# Controle_placa_potencia.net
KiCad netlist of a schematic drawn in Altium Designer
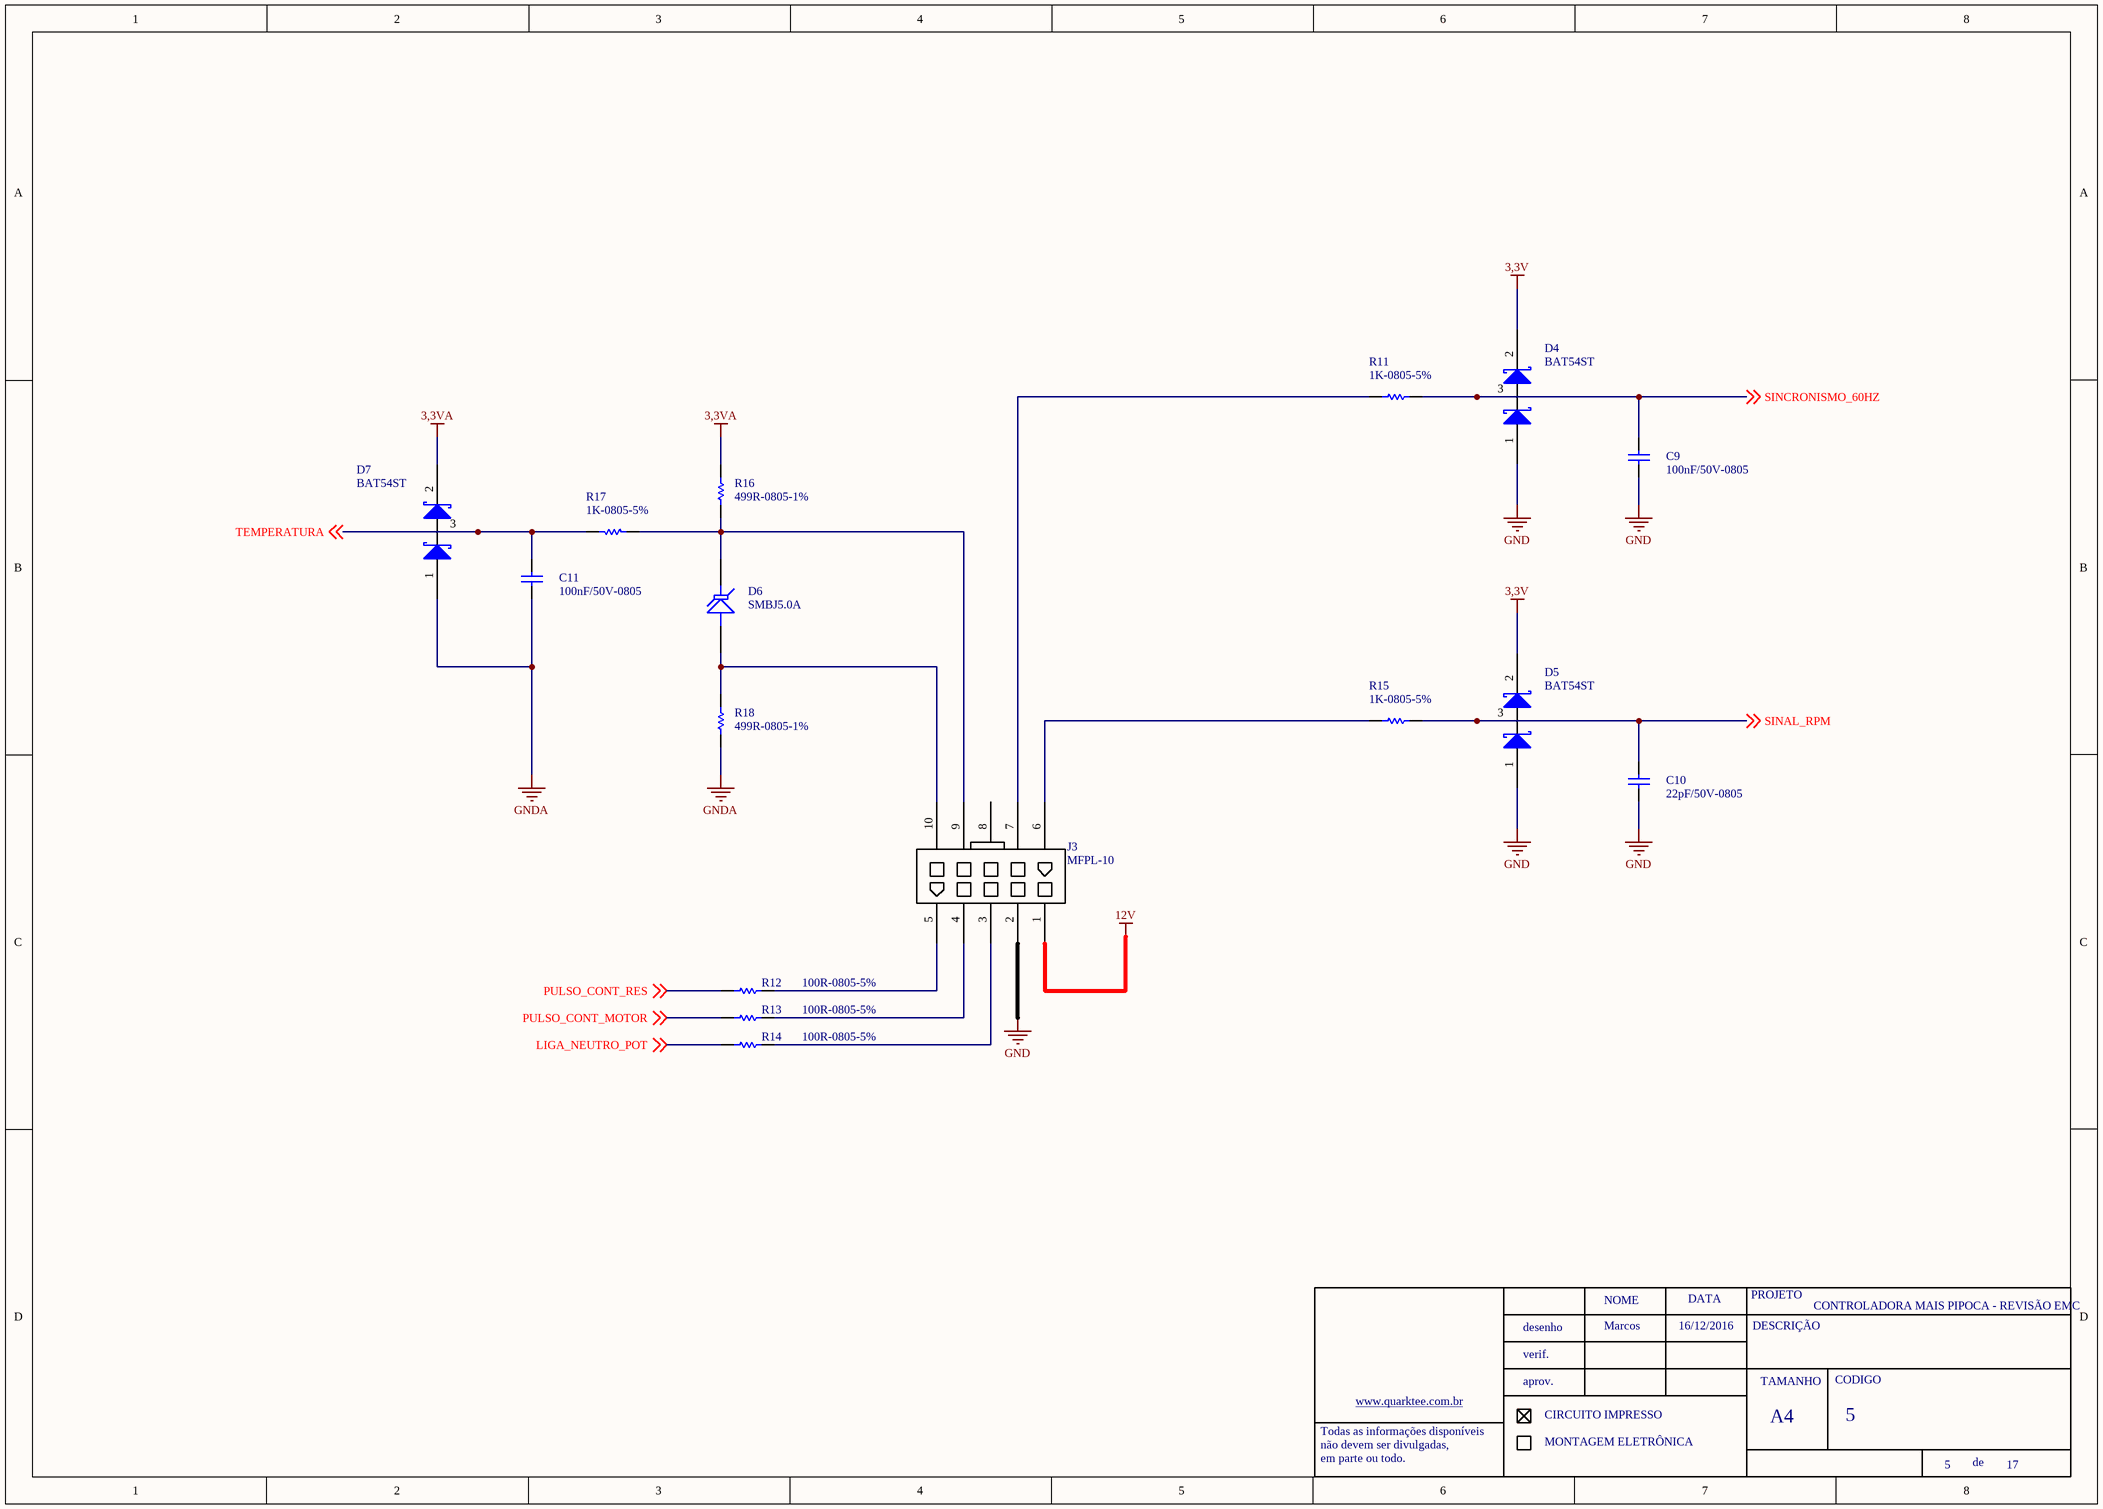
[diagram p0: Controle_placa_potencia.SchDoc]

(export (version "E")
  (design (tool "Eeschema 10.0.6"))
  (components
    (comp (ref "C9")
      (value "100nF/50V-0805")
      (footprint "0805-REVISADO ONDA")
      (libsource (lib "AquinoLib") (part "100nF/50-0805-NPO"))
    )
    (comp (ref "C10")
      (value "22pF/50V-0805")
      (footprint "0805-REVISADO ONDA")
      (description "100nF/50V-0805")
      (libsource (lib "AquinoLib") (part "100nF/50-0805-NPO"))
    )
    (comp (ref "C11")
      (value "100nF/50V-0805")
      (footprint "0805-REVISADO ONDA")
      (libsource (lib "AquinoLib") (part "100nF/50-0805-NPO"))
    )
    (comp (ref "D4")
      (value "BAT54ST")
      (footprint "SOT23 - REVISADO ONDA")
      (libsource (lib "AquinoLib") (part "BAT54ST"))
    )
    (comp (ref "D5")
      (value "BAT54ST")
      (footprint "SOT23 - REVISADO ONDA")
      (libsource (lib "AquinoLib") (part "BAT54ST"))
    )
    (comp (ref "D6")
      (value "SMBJ5.0A")
      (footprint "SMA DIODES")
      (libsource (lib "AquinoLib") (part "SMBJ5.0A"))
    )
    (comp (ref "D7")
      (value "BAT54ST")
      (footprint "SOT23 - REVISADO ONDA")
      (libsource (lib "AquinoLib") (part "BAT54ST"))
    )
    (comp (ref "J3") (value "MFPL-10") (libsource (lib "AquinoLib") (part "MFPL-10")))
    (comp (ref "R11")
      (value "1K-0805-5%")
      (footprint "0805-REVISADO ONDA")
      (libsource (lib "AquinoLib") (part "1K-0805-5%"))
    )
    (comp (ref "R12")
      (value "100R-0805-5%")
      (footprint "0805-REVISADO ONDA")
      (libsource (lib "AquinoLib") (part "100R-0805-5%"))
    )
    (comp (ref "R13")
      (value "100R-0805-5%")
      (footprint "0805-REVISADO ONDA")
      (libsource (lib "AquinoLib") (part "100R-0805-5%"))
    )
    (comp (ref "R14")
      (value "100R-0805-5%")
      (footprint "0805-REVISADO ONDA")
      (libsource (lib "AquinoLib") (part "100R-0805-5%"))
    )
    (comp (ref "R15")
      (value "1K-0805-5%")
      (footprint "0805-REVISADO ONDA")
      (libsource (lib "AquinoLib") (part "1K-0805-5%"))
    )
    (comp (ref "R16")
      (value "499R-0805-1%")
      (footprint "0805-REVISADO ONDA")
      (description "10K-0805-5%")
      (libsource (lib "AquinoLib") (part "10K-0805-5%"))
    )
    (comp (ref "R17")
      (value "1K-0805-5%")
      (footprint "0805-REVISADO ONDA")
      (libsource (lib "AquinoLib") (part "1K-0805-5%"))
    )
    (comp (ref "R18")
      (value "499R-0805-1%")
      (footprint "0805-REVISADO ONDA")
      (description "10K-0805-5%")
      (libsource (lib "AquinoLib") (part "10K-0805-5%"))
    )
  )
  (nets
    (net (code "1") (name "3,3V") (class "Default")
      (node (ref "D4") (pin "2") (pinfunction "2_2") (pintype "passive"))
      (node (ref "D5") (pin "2") (pinfunction "2_2") (pintype "passive"))
    )
    (net (code "2") (name "3,3VA") (class "Default")
      (node (ref "D7") (pin "2") (pinfunction "2_2") (pintype "passive"))
      (node (ref "R16") (pin "2") (pinfunction "2_2") (pintype "passive"))
    )
    (net (code "3") (name "12V") (class "Default")
      (node (ref "J3") (pin "1") (pinfunction "1_1") (pintype "passive"))
    )
    (net (code "4") (name "GND") (class "Default")
      (node (ref "C10") (pin "2") (pinfunction "2_2") (pintype "passive"))
      (node (ref "C9") (pin "2") (pinfunction "2_2") (pintype "passive"))
      (node (ref "D4") (pin "1") (pinfunction "1_1") (pintype "passive"))
      (node (ref "D5") (pin "1") (pinfunction "1_1") (pintype "passive"))
      (node (ref "J3") (pin "2") (pinfunction "2_2") (pintype "passive"))
    )
    (net (code "5") (name "GNDA") (class "Default")
      (node (ref "C11") (pin "1") (pinfunction "1_1") (pintype "passive"))
      (node (ref "D7") (pin "1") (pinfunction "1_1") (pintype "passive"))
      (node (ref "R18") (pin "1") (pinfunction "1_1") (pintype "passive"))
    )
    (net (code "6") (name "LIGA_NEUTRO_POT") (class "Default")
      (node (ref "R14") (pin "1") (pinfunction "1_1") (pintype "passive"))
    )
    (net (code "7") (name "Net-(D6-A)") (class "Default")
      (node (ref "D6") (pin "1") (pinfunction "A_1") (pintype "passive"))
      (node (ref "J3") (pin "10") (pinfunction "10_10") (pintype "passive"))
      (node (ref "R18") (pin "2") (pinfunction "2_2") (pintype "passive"))
    )
    (net (code "8") (name "Net-(D6-K)") (class "Default")
      (node (ref "D6") (pin "2") (pinfunction "K_2") (pintype "passive"))
      (node (ref "J3") (pin "9") (pinfunction "9_9") (pintype "passive"))
      (node (ref "R16") (pin "1") (pinfunction "1_1") (pintype "passive"))
      (node (ref "R17") (pin "1") (pinfunction "1_1") (pintype "passive"))
    )
    (net (code "9") (name "Net-(J3-Pad3)") (class "Default")
      (node (ref "J3") (pin "3") (pinfunction "3_3") (pintype "passive"))
      (node (ref "R14") (pin "2") (pinfunction "2_2") (pintype "passive"))
    )
    (net (code "10") (name "Net-(J3-Pad4)") (class "Default")
      (node (ref "J3") (pin "4") (pinfunction "4_4") (pintype "passive"))
      (node (ref "R13") (pin "2") (pinfunction "2_2") (pintype "passive"))
    )
    (net (code "11") (name "Net-(J3-Pad5)") (class "Default")
      (node (ref "J3") (pin "5") (pinfunction "5_5") (pintype "passive"))
      (node (ref "R12") (pin "1") (pinfunction "1_1") (pintype "passive"))
    )
    (net (code "12") (name "Net-(J3-Pad6)") (class "Default")
      (node (ref "J3") (pin "6") (pinfunction "6_6") (pintype "passive"))
      (node (ref "R15") (pin "1") (pinfunction "1_1") (pintype "passive"))
    )
    (net (code "13") (name "Net-(J3-Pad7)") (class "Default")
      (node (ref "J3") (pin "7") (pinfunction "7_7") (pintype "passive"))
      (node (ref "R11") (pin "1") (pinfunction "1_1") (pintype "passive"))
    )
    (net (code "14") (name "PULSO_CONT_MOTOR") (class "Default")
      (node (ref "R13") (pin "1") (pinfunction "1_1") (pintype "passive"))
    )
    (net (code "15") (name "PULSO_CONT_RES") (class "Default")
      (node (ref "R12") (pin "2") (pinfunction "2_2") (pintype "passive"))
    )
    (net (code "16") (name "SINAL_RPM") (class "Default")
      (node (ref "C10") (pin "1") (pinfunction "1_1") (pintype "passive"))
      (node (ref "D5") (pin "3") (pinfunction "3_3") (pintype "passive"))
      (node (ref "R15") (pin "2") (pinfunction "2_2") (pintype "passive"))
    )
    (net (code "17") (name "SINCRONISMO_60HZ") (class "Default")
      (node (ref "C9") (pin "1") (pinfunction "1_1") (pintype "passive"))
      (node (ref "D4") (pin "3") (pinfunction "3_3") (pintype "passive"))
      (node (ref "R11") (pin "2") (pinfunction "2_2") (pintype "passive"))
    )
    (net (code "18") (name "TEMPERATURA") (class "Default")
      (node (ref "C11") (pin "2") (pinfunction "2_2") (pintype "passive"))
      (node (ref "D7") (pin "3") (pinfunction "3_3") (pintype "passive"))
      (node (ref "R17") (pin "2") (pinfunction "2_2") (pintype "passive"))
    )
    (net (code "19") (name "unconnected-(J3-Pad8)") (class "Default")
      (node (ref "J3") (pin "8") (pinfunction "8_8") (pintype "passive"))
    )
  )
)
